# depth_sensor.net
KiCad netlist of a schematic drawn in Altium Designer
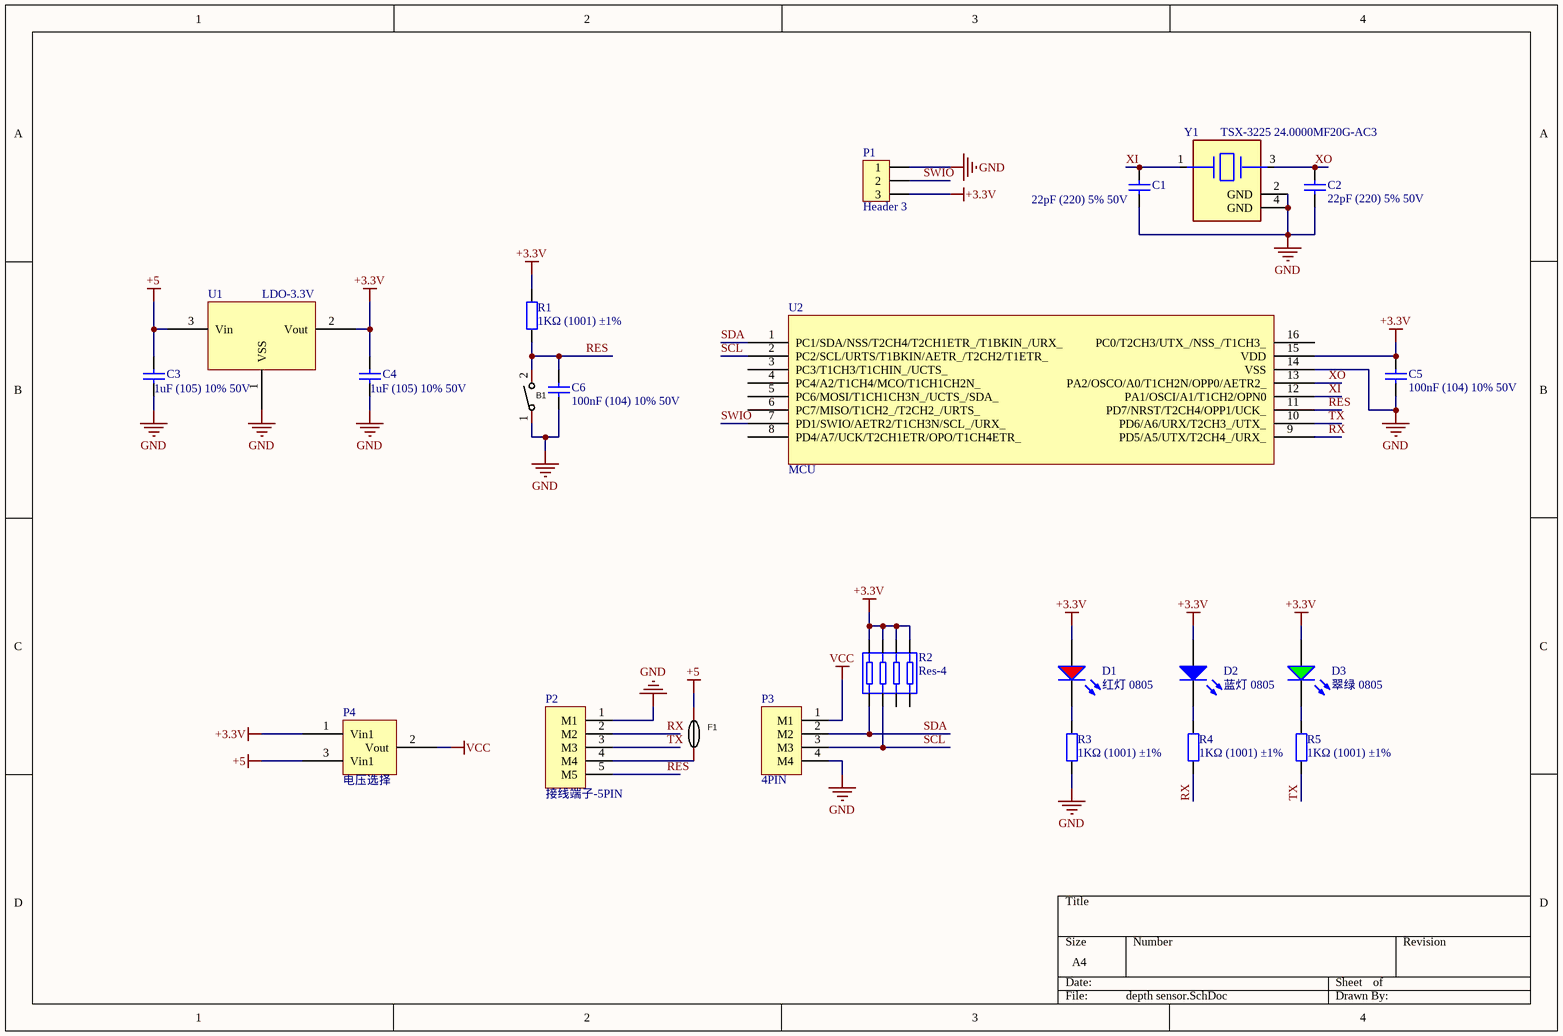
[diagram p0: depth sensor.SchDoc]

(export (version "E")
  (design (tool "Eeschema 10.0.6"))
  (components
    (comp (ref "B1")
      (value "TS342A2P-WZ")
      (footprint "SW-SMD_L4.0-W2.9-LS5.0")
      (fields (field (name "MANUFACTURER") "SHOU HAN(首韩)"))
      (libsource (lib "Stm32Basic") (part "TS342A2P-WZ"))
    )
    (comp (ref "C1")
      (value "22pF (220) 5% 50V")
      (footprint "0603_C")
      (description "贴片电容")
      (libsource (lib "Cap") (part "0603 22pF (220) 5% 50V"))
    )
    (comp (ref "C2")
      (value "22pF (220) 5% 50V")
      (footprint "0603_C")
      (description "贴片电容")
      (libsource (lib "Cap") (part "0603 22pF (220) 5% 50V"))
    )
    (comp (ref "C3")
      (value "1uF (105) 10% 50V")
      (footprint "0603_C")
      (description "贴片电容")
      (libsource (lib "Cap") (part "0603 1uF (105) 10% 50V"))
    )
    (comp (ref "C4")
      (value "1uF (105) 10% 50V")
      (footprint "0603_C")
      (description "贴片电容")
      (libsource (lib "Cap") (part "0603 1uF (105) 10% 50V"))
    )
    (comp (ref "C5")
      (value "100nF (104) 10% 50V")
      (footprint "0603_C")
      (description "贴片电容")
      (libsource (lib "Cap") (part "0603 100nF (104) 10% 50V"))
    )
    (comp (ref "C6")
      (value "100nF (104) 10% 50V")
      (footprint "0603_C")
      (description "贴片电容")
      (libsource (lib "Cap") (part "0603 100nF (104) 10% 50V"))
    )
    (comp (ref "D1")
      (value "红灯 0805")
      (footprint "0805_LED_S1")
      (description "发光二极管")
      (libsource (lib "LED") (part "0805 红灯"))
    )
    (comp (ref "D2")
      (value "蓝灯 0805")
      (footprint "0805_LED_S1")
      (description "发光二极管")
      (libsource (lib "LED") (part "0805 蓝灯"))
    )
    (comp (ref "D3")
      (value "翠绿 0805")
      (footprint "0805_LED_S1")
      (description "发光二极管")
      (libsource (lib "LED") (part "0805 翠绿"))
    )
    (comp (ref "F1")
      (value "SMD0805-110")
      (footprint "F0805")
      (fields (field (name "MANUFACTURER") "DOWO(东沃)"))
      (libsource (lib "Stm32Basic") (part "SMD0805-110"))
    )
    (comp (ref "P1")
      (value "Header 3")
      (footprint "Header 3")
      (description "排针")
      (libsource (lib "集大电协1.5") (part "Header 3"))
    )
    (comp (ref "P2")
      (value "接线端子-5PIN")
      (footprint "PH2.0-WS-5P")
      (libsource (lib "集大电协1.5") (part "接线端子-5PIN"))
    )
    (comp (ref "P3")
      (value "4PIN")
      (footprint "MX1.25WS-4PIN")
      (libsource (lib "集大电协1.5") (part "接线端子-4PIN"))
    )
    (comp (ref "P4") (value "电压选择") (footprint "change") (libsource (lib "depth sensor") (part "电压选择")))
    (comp (ref "R1")
      (value "1KΩ (1001) ±1%")
      (footprint "0603_R")
      (description "贴片电阻")
      (libsource (lib "RES") (part "0603 1KΩ (1001) 1%"))
    )
    (comp (ref "R2")
      (value "Res-4")
      (footprint "res-4")
      (description "排阻")
      (libsource (lib "集大电协1.5") (part "Res-4"))
    )
    (comp (ref "R3")
      (value "1KΩ (1001) ±1%")
      (footprint "0603_R")
      (description "贴片电阻")
      (libsource (lib "RES") (part "0603 1KΩ (1001) 1%"))
    )
    (comp (ref "R4")
      (value "1KΩ (1001) ±1%")
      (footprint "0603_R")
      (description "贴片电阻")
      (libsource (lib "RES") (part "0603 1KΩ (1001) 1%"))
    )
    (comp (ref "R5")
      (value "1KΩ (1001) ±1%")
      (footprint "0603_R")
      (description "贴片电阻")
      (libsource (lib "RES") (part "0603 1KΩ (1001) 1%"))
    )
    (comp (ref "U1")
      (value "LDO-3.3V")
      (footprint "SOT95P290X110-3N")
      (libsource (lib "depth sensor") (part "CE6219"))
    )
    (comp (ref "U2")
      (value "MCU")
      (footprint "TSOP127P600X155-16N")
      (libsource (lib "depth sensor") (part "CH32V003A4M6"))
    )
    (comp (ref "Y1")
      (value "TSX-3225 24.0000MF20G-AC3")
      (footprint "FP-TSX-3225-MFG")
      (description "CRYSTAL 24.0000MHZ 9PF SMD")
      (fields (field (name "TOLERANCE") "10ppm"))
      (libsource (lib "Altium Content Vault") (part "862d5228ea4a4c8f16e8fb874e464c7"))
    )
  )
  (nets
    (net (code "1") (name "+3.3V") (class "Default")
      (node (ref "C4") (pin "2") (pinfunction "2_2") (pintype "passive"))
      (node (ref "C5") (pin "2") (pinfunction "2_2") (pintype "passive"))
      (node (ref "D1") (pin "A") (pinfunction "A_A") (pintype "passive"))
      (node (ref "D2") (pin "A") (pinfunction "A_A") (pintype "passive"))
      (node (ref "D3") (pin "A") (pinfunction "A_A") (pintype "passive"))
      (node (ref "P1") (pin "3") (pinfunction "3_3") (pintype "passive"))
      (node (ref "P4") (pin "1") (pinfunction "Vin1_1") (pintype "passive"))
      (node (ref "R1") (pin "2") (pinfunction "2_2") (pintype "passive"))
      (node (ref "R2") (pin "5") (pinfunction "5_5") (pintype "passive"))
      (node (ref "R2") (pin "6") (pinfunction "6_6") (pintype "passive"))
      (node (ref "R2") (pin "7") (pinfunction "7_7") (pintype "passive"))
      (node (ref "R2") (pin "8") (pinfunction "8_8") (pintype "passive"))
      (node (ref "U1") (pin "2") (pinfunction "Vout_2") (pintype "passive"))
      (node (ref "U2") (pin "15") (pinfunction "VDD_15") (pintype "passive"))
    )
    (net (code "2") (name "+5") (class "Default")
      (node (ref "C3") (pin "2") (pinfunction "2_2") (pintype "passive"))
      (node (ref "F1") (pin "2") (pinfunction "2_2") (pintype "passive"))
      (node (ref "P4") (pin "3") (pinfunction "Vin1_3") (pintype "passive"))
      (node (ref "U1") (pin "3") (pinfunction "Vin_3") (pintype "passive"))
    )
    (net (code "3") (name "/RES") (class "Default")
      (node (ref "B1") (pin "2") (pinfunction "2_2") (pintype "passive"))
      (node (ref "C6") (pin "2") (pinfunction "2_2") (pintype "passive"))
      (node (ref "P2") (pin "5") (pinfunction "M5_5") (pintype "passive"))
      (node (ref "R1") (pin "1") (pinfunction "1_1") (pintype "passive"))
      (node (ref "U2") (pin "11") (pinfunction "PD7/NRST/T2CH4/OPP1/UCK__11") (pintype "passive"))
    )
    (net (code "4") (name "/RX") (class "Default")
      (node (ref "P2") (pin "2") (pinfunction "M2_2") (pintype "passive"))
      (node (ref "R4") (pin "1") (pinfunction "1_1") (pintype "passive"))
      (node (ref "U2") (pin "9") (pinfunction "PD5/A5/UTX/T2CH4_/URX__9") (pintype "passive"))
    )
    (net (code "5") (name "/SCL") (class "Default")
      (node (ref "P3") (pin "3") (pinfunction "M3_3") (pintype "passive"))
      (node (ref "R2") (pin "2") (pinfunction "2_2") (pintype "passive"))
      (node (ref "U2") (pin "2") (pinfunction "PC2/SCL/URTS/T1BKIN/AETR_/T2CH2/T1ETR__2") (pintype "passive"))
    )
    (net (code "6") (name "/SDA") (class "Default")
      (node (ref "P3") (pin "2") (pinfunction "M2_2") (pintype "passive"))
      (node (ref "R2") (pin "1") (pinfunction "1_1") (pintype "passive"))
      (node (ref "U2") (pin "1") (pinfunction "PC1/SDA/NSS/T2CH4/T2CH1ETR_/T1BKIN_/URX__1") (pintype "passive"))
    )
    (net (code "7") (name "/SWIO") (class "Default")
      (node (ref "P1") (pin "2") (pinfunction "2_2") (pintype "passive"))
      (node (ref "U2") (pin "7") (pinfunction "PD1/SWIO/AETR2/T1CH3N/SCL_/URX__7") (pintype "passive"))
    )
    (net (code "8") (name "/TX") (class "Default")
      (node (ref "P2") (pin "3") (pinfunction "M3_3") (pintype "passive"))
      (node (ref "R5") (pin "1") (pinfunction "1_1") (pintype "passive"))
      (node (ref "U2") (pin "10") (pinfunction "PD6/A6/URX/T2CH3_/UTX__10") (pintype "passive"))
    )
    (net (code "9") (name "/XI") (class "Default")
      (node (ref "C1") (pin "2") (pinfunction "2_2") (pintype "passive"))
      (node (ref "U2") (pin "12") (pinfunction "PA1/OSCI/A1/T1CH2/OPN0_12") (pintype "passive"))
      (node (ref "Y1") (pin "1") (pinfunction "1_1") (pintype "passive"))
    )
    (net (code "10") (name "/XO") (class "Default")
      (node (ref "C2") (pin "2") (pinfunction "2_2") (pintype "passive"))
      (node (ref "U2") (pin "13") (pinfunction "PA2/OSCO/A0/T1CH2N/OPP0/AETR2__13") (pintype "passive"))
      (node (ref "Y1") (pin "3") (pinfunction "3_3") (pintype "passive"))
    )
    (net (code "11") (name "GND") (class "Default")
      (node (ref "B1") (pin "1") (pinfunction "1_1") (pintype "passive"))
      (node (ref "C1") (pin "1") (pinfunction "1_1") (pintype "passive"))
      (node (ref "C2") (pin "1") (pinfunction "1_1") (pintype "passive"))
      (node (ref "C3") (pin "1") (pinfunction "1_1") (pintype "passive"))
      (node (ref "C4") (pin "1") (pinfunction "1_1") (pintype "passive"))
      (node (ref "C5") (pin "1") (pinfunction "1_1") (pintype "passive"))
      (node (ref "C6") (pin "1") (pinfunction "1_1") (pintype "passive"))
      (node (ref "P1") (pin "1") (pinfunction "1_1") (pintype "passive"))
      (node (ref "P2") (pin "1") (pinfunction "M1_1") (pintype "passive"))
      (node (ref "P3") (pin "4") (pinfunction "M4_4") (pintype "passive"))
      (node (ref "R3") (pin "1") (pinfunction "1_1") (pintype "passive"))
      (node (ref "U1") (pin "1") (pinfunction "VSS_1") (pintype "passive"))
      (node (ref "U2") (pin "14") (pinfunction "VSS_14") (pintype "passive"))
      (node (ref "Y1") (pin "2") (pinfunction "GND_2") (pintype "power_in"))
      (node (ref "Y1") (pin "4") (pinfunction "GND_4") (pintype "power_in"))
    )
    (net (code "12") (name "Net-(D1-PadK)") (class "Default")
      (node (ref "D1") (pin "K") (pinfunction "K_K") (pintype "passive"))
      (node (ref "R3") (pin "2") (pinfunction "2_2") (pintype "passive"))
    )
    (net (code "13") (name "Net-(D2-PadK)") (class "Default")
      (node (ref "D2") (pin "K") (pinfunction "K_K") (pintype "passive"))
      (node (ref "R4") (pin "2") (pinfunction "2_2") (pintype "passive"))
    )
    (net (code "14") (name "Net-(D3-PadK)") (class "Default")
      (node (ref "D3") (pin "K") (pinfunction "K_K") (pintype "passive"))
      (node (ref "R5") (pin "2") (pinfunction "2_2") (pintype "passive"))
    )
    (net (code "15") (name "Net-(P2-M4)") (class "Default")
      (node (ref "F1") (pin "1") (pinfunction "1_1") (pintype "passive"))
      (node (ref "P2") (pin "4") (pinfunction "M4_4") (pintype "passive"))
    )
    (net (code "16") (name "VCC") (class "Default")
      (node (ref "P3") (pin "1") (pinfunction "M1_1") (pintype "passive"))
      (node (ref "P4") (pin "2") (pinfunction "Vout_2") (pintype "passive"))
    )
    (net (code "17") (name "unconnected-(R2-Pad3)") (class "Default")
      (node (ref "R2") (pin "3") (pinfunction "3_3") (pintype "passive"))
    )
    (net (code "18") (name "unconnected-(R2-Pad4)") (class "Default")
      (node (ref "R2") (pin "4") (pinfunction "4_4") (pintype "passive"))
    )
    (net (code "19") (name "unconnected-(U2-PC0{slash}T2CH3{slash}UTX_{slash}NSS_{slash}T1CH3_-Pad16)") (class "Default")
      (node (ref "U2") (pin "16") (pinfunction "PC0/T2CH3/UTX_/NSS_/T1CH3__16") (pintype "passive"))
    )
    (net (code "20") (name "unconnected-(U2-PC3{slash}T1CH3{slash}T1CHIN_{slash}UCTS_-Pad3)") (class "Default")
      (node (ref "U2") (pin "3") (pinfunction "PC3/T1CH3/T1CHIN_/UCTS__3") (pintype "passive"))
    )
    (net (code "21") (name "unconnected-(U2-PC4{slash}A2{slash}T1CH4{slash}MCO{slash}T1CH1CH2N_-Pad4)") (class "Default")
      (node (ref "U2") (pin "4") (pinfunction "PC4/A2/T1CH4/MCO/T1CH1CH2N__4") (pintype "passive"))
    )
    (net (code "22") (name "unconnected-(U2-PC6{slash}MOSI{slash}T1CH1CH3N_{slash}UCTS_{slash}SDA_-Pad5)") (class "Default")
      (node (ref "U2") (pin "5") (pinfunction "PC6/MOSI/T1CH1CH3N_/UCTS_/SDA__5") (pintype "passive"))
    )
    (net (code "23") (name "unconnected-(U2-PC7{slash}MISO{slash}T1CH2_{slash}T2CH2_{slash}URTS_-Pad6)") (class "Default")
      (node (ref "U2") (pin "6") (pinfunction "PC7/MISO/T1CH2_/T2CH2_/URTS__6") (pintype "passive"))
    )
    (net (code "24") (name "unconnected-(U2-PD4{slash}A7{slash}UCK{slash}T2CH1ETR{slash}OPO{slash}T1CH4ETR_-Pad8)") (class "Default")
      (node (ref "U2") (pin "8") (pinfunction "PD4/A7/UCK/T2CH1ETR/OPO/T1CH4ETR__8") (pintype "passive"))
    )
  )
)
